# 13_EEPROM_SW_JTAG.net
KiCad netlist of a schematic drawn in Altium Designer
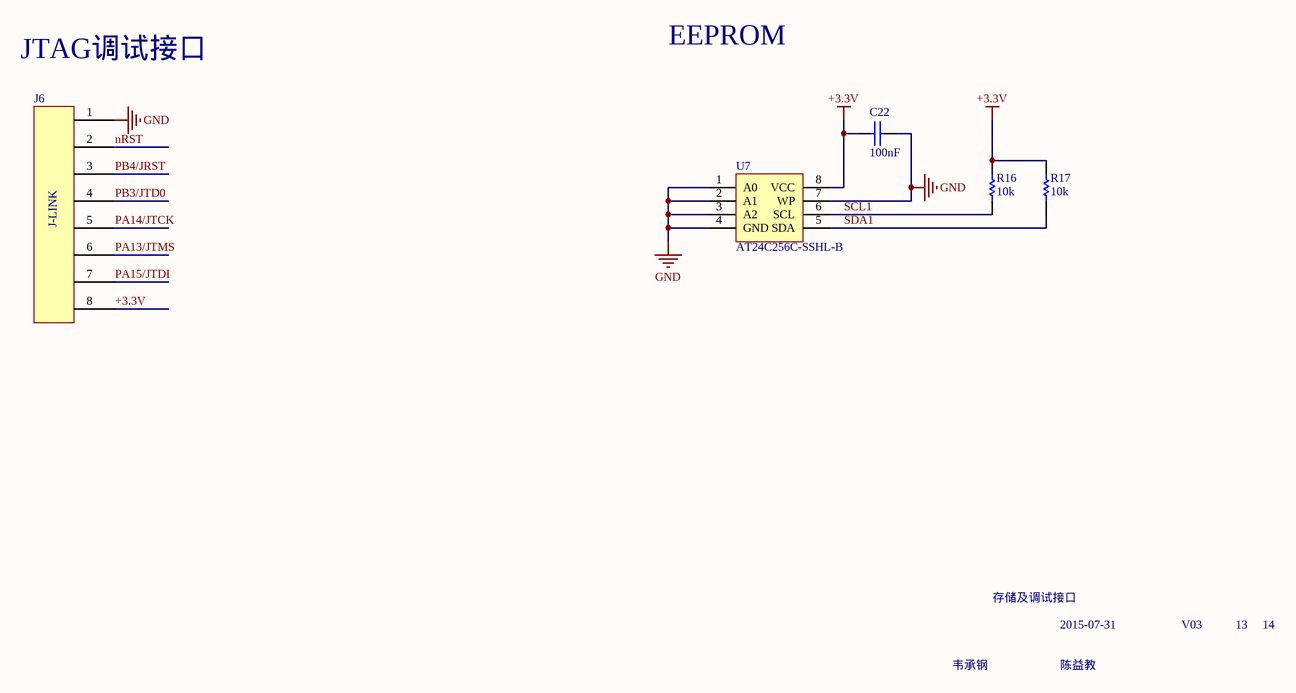
[diagram p0: 13_EEPROM_SW_JTAG.SchDoc]

(export (version "E")
  (design (tool "Eeschema 10.0.6"))
  (components
    (comp (ref "C22") (value "100nF") (footprint "0603C") (libsource (lib "WeiCHGSCH") (part "CAP")))
    (comp (ref "J6") (value "J-LINK") (footprint "JA4/2/3") (libsource (lib "*") (part "COM8")))
    (comp (ref "R16") (value "10k") (footprint "0603R") (libsource (lib "Mylibrary") (part "RES")))
    (comp (ref "R17") (value "10k") (footprint "0603R") (libsource (lib "Mylibrary") (part "RES")))
    (comp (ref "U7")
      (value "AT24C256C-SSHL-B")
      (footprint "SOP8")
      (libsource (lib "WeiCHGSCH") (part "24CXX"))
    )
  )
  (nets
    (net (code "1") (name "+3.3V") (class "Default")
      (node (ref "C22") (pin "1") (pinfunction "1_1") (pintype "passive"))
      (node (ref "J6") (pin "8") (pinfunction "8_8") (pintype "passive"))
      (node (ref "R16") (pin "2") (pinfunction "2_2") (pintype "passive"))
      (node (ref "R17") (pin "2") (pinfunction "2_2") (pintype "passive"))
      (node (ref "U7") (pin "8") (pinfunction "VCC_8") (pintype "passive"))
    )
    (net (code "2") (name "/PA13{slash}JTMS") (class "Default")
      (node (ref "J6") (pin "6") (pinfunction "6_6") (pintype "passive"))
    )
    (net (code "3") (name "/PA14{slash}JTCK") (class "Default")
      (node (ref "J6") (pin "5") (pinfunction "5_5") (pintype "passive"))
    )
    (net (code "4") (name "/PA15{slash}JTDI") (class "Default")
      (node (ref "J6") (pin "7") (pinfunction "7_7") (pintype "passive"))
    )
    (net (code "5") (name "/PB3{slash}JTD0") (class "Default")
      (node (ref "J6") (pin "4") (pinfunction "4_4") (pintype "passive"))
    )
    (net (code "6") (name "/PB4{slash}JRST") (class "Default")
      (node (ref "J6") (pin "3") (pinfunction "3_3") (pintype "passive"))
    )
    (net (code "7") (name "/SCL1") (class "Default")
      (node (ref "R16") (pin "1") (pinfunction "1_1") (pintype "passive"))
      (node (ref "U7") (pin "6") (pinfunction "SCL_6") (pintype "passive"))
    )
    (net (code "8") (name "/SDA1") (class "Default")
      (node (ref "R17") (pin "1") (pinfunction "1_1") (pintype "passive"))
      (node (ref "U7") (pin "5") (pinfunction "SDA_5") (pintype "passive"))
    )
    (net (code "9") (name "/nRST") (class "Default")
      (node (ref "J6") (pin "2") (pinfunction "2_2") (pintype "passive"))
    )
    (net (code "10") (name "GND") (class "Default")
      (node (ref "C22") (pin "2") (pinfunction "2_2") (pintype "passive"))
      (node (ref "J6") (pin "1") (pinfunction "1_1") (pintype "passive"))
      (node (ref "U7") (pin "1") (pinfunction "A0_1") (pintype "passive"))
      (node (ref "U7") (pin "2") (pinfunction "A1_2") (pintype "passive"))
      (node (ref "U7") (pin "3") (pinfunction "A2_3") (pintype "passive"))
      (node (ref "U7") (pin "4") (pinfunction "GND_4") (pintype "passive"))
      (node (ref "U7") (pin "7") (pinfunction "WP_7") (pintype "passive"))
    )
  )
)
